# Connector_SFP.net
KiCad netlist of a schematic drawn in Altium Designer
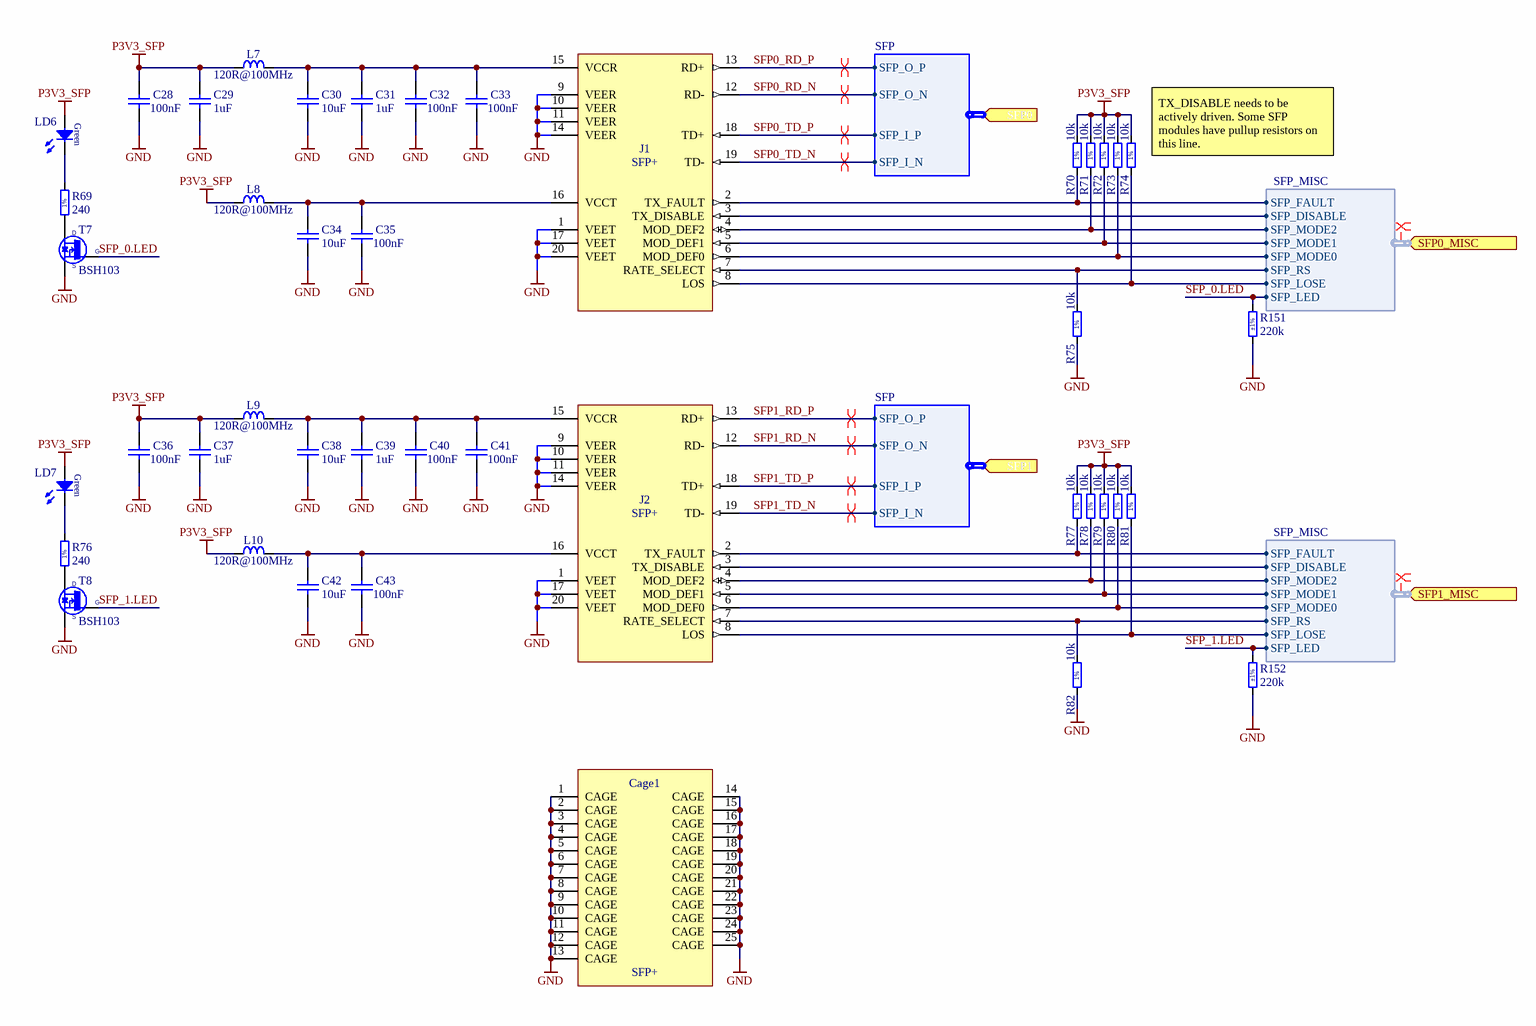
[diagram p0: Connector_SFP.SchDoc]

(export (version "E")
  (design (tool "Eeschema 10.0.6"))
  (components
    (comp (ref "C28")
      (value "100nF")
      (footprint "CAPC1005X55N")
      (description "Non-polarised capacitor")
      (fields
        (field (name "PART NUMBER") "CC0402_100NF_16V_10%_X5R")
        (field (name "VOLTAGE") "16V")
        (field (name "AUTHOR") "CERN DEM JLC")
      )
      (libsource (lib "Capacitors") (part "Capacitor - non polarized"))
    )
    (comp (ref "C29")
      (value "1uF")
      (footprint "CAPC1005X55N")
      (description "Non-polarised capacitor")
      (fields
        (field (name "PART NUMBER") "CC0402_1UF_16V_10%_X5R")
        (field (name "VOLTAGE") "16V")
        (field (name "AUTHOR") "CERN DEM JLC")
      )
      (libsource (lib "Capacitors") (part "Capacitor - non polarized"))
    )
    (comp (ref "C30")
      (value "10uF")
      (footprint "CAPC1608X80N")
      (description "Non-polarised capacitor")
      (fields
        (field (name "PART NUMBER") "CC0603_10UF_16V_20%_X5R")
        (field (name "VOLTAGE") "16V")
        (field (name "AUTHOR") "CERN DEM MR")
      )
      (libsource (lib "Capacitors") (part "Capacitor - non polarized"))
    )
    (comp (ref "C31")
      (value "1uF")
      (footprint "CAPC1005X55N")
      (description "Non-polarised capacitor")
      (fields
        (field (name "PART NUMBER") "CC0402_1UF_16V_10%_X5R")
        (field (name "VOLTAGE") "16V")
        (field (name "AUTHOR") "CERN DEM JLC")
      )
      (libsource (lib "Capacitors") (part "Capacitor - non polarized"))
    )
    (comp (ref "C32")
      (value "100nF")
      (footprint "CAPC1005X55N")
      (description "Non-polarised capacitor")
      (fields
        (field (name "PART NUMBER") "CC0402_100NF_16V_10%_X5R")
        (field (name "VOLTAGE") "16V")
        (field (name "AUTHOR") "CERN DEM JLC")
      )
      (libsource (lib "Capacitors") (part "Capacitor - non polarized"))
    )
    (comp (ref "C33")
      (value "100nF")
      (footprint "CAPC1005X55N")
      (description "Non-polarised capacitor")
      (fields
        (field (name "PART NUMBER") "CC0402_100NF_16V_10%_X5R")
        (field (name "VOLTAGE") "16V")
        (field (name "AUTHOR") "CERN DEM JLC")
      )
      (libsource (lib "Capacitors") (part "Capacitor - non polarized"))
    )
    (comp (ref "C34")
      (value "10uF")
      (footprint "CAPC1608X80N")
      (description "Non-polarised capacitor")
      (fields
        (field (name "PART NUMBER") "CC0603_10UF_16V_20%_X5R")
        (field (name "VOLTAGE") "16V")
        (field (name "AUTHOR") "CERN DEM MR")
      )
      (libsource (lib "Capacitors") (part "Capacitor - non polarized"))
    )
    (comp (ref "C35")
      (value "100nF")
      (footprint "CAPC1005X55N")
      (description "Non-polarised capacitor")
      (fields
        (field (name "PART NUMBER") "CC0402_100NF_16V_10%_X5R")
        (field (name "VOLTAGE") "16V")
        (field (name "AUTHOR") "CERN DEM JLC")
      )
      (libsource (lib "Capacitors") (part "Capacitor - non polarized"))
    )
    (comp (ref "C36")
      (value "100nF")
      (footprint "CAPC1005X55N")
      (description "Non-polarised capacitor")
      (fields
        (field (name "PART NUMBER") "CC0402_100NF_16V_10%_X5R")
        (field (name "VOLTAGE") "16V")
        (field (name "AUTHOR") "CERN DEM JLC")
      )
      (libsource (lib "Capacitors") (part "Capacitor - non polarized"))
    )
    (comp (ref "C37")
      (value "1uF")
      (footprint "CAPC1005X55N")
      (description "Non-polarised capacitor")
      (fields
        (field (name "PART NUMBER") "CC0402_1UF_16V_10%_X5R")
        (field (name "VOLTAGE") "16V")
        (field (name "AUTHOR") "CERN DEM JLC")
      )
      (libsource (lib "Capacitors") (part "Capacitor - non polarized"))
    )
    (comp (ref "C38")
      (value "10uF")
      (footprint "CAPC1608X80N")
      (description "Non-polarised capacitor")
      (fields
        (field (name "PART NUMBER") "CC0603_10UF_16V_20%_X5R")
        (field (name "VOLTAGE") "16V")
        (field (name "AUTHOR") "CERN DEM MR")
      )
      (libsource (lib "Capacitors") (part "Capacitor - non polarized"))
    )
    (comp (ref "C39")
      (value "1uF")
      (footprint "CAPC1005X55N")
      (description "Non-polarised capacitor")
      (fields
        (field (name "PART NUMBER") "CC0402_1UF_16V_10%_X5R")
        (field (name "VOLTAGE") "16V")
        (field (name "AUTHOR") "CERN DEM JLC")
      )
      (libsource (lib "Capacitors") (part "Capacitor - non polarized"))
    )
    (comp (ref "C40")
      (value "100nF")
      (footprint "CAPC1005X55N")
      (description "Non-polarised capacitor")
      (fields
        (field (name "PART NUMBER") "CC0402_100NF_16V_10%_X5R")
        (field (name "VOLTAGE") "16V")
        (field (name "AUTHOR") "CERN DEM JLC")
      )
      (libsource (lib "Capacitors") (part "Capacitor - non polarized"))
    )
    (comp (ref "C41")
      (value "100nF")
      (footprint "CAPC1005X55N")
      (description "Non-polarised capacitor")
      (fields
        (field (name "PART NUMBER") "CC0402_100NF_16V_10%_X5R")
        (field (name "VOLTAGE") "16V")
        (field (name "AUTHOR") "CERN DEM JLC")
      )
      (libsource (lib "Capacitors") (part "Capacitor - non polarized"))
    )
    (comp (ref "C42")
      (value "10uF")
      (footprint "CAPC1608X80N")
      (description "Non-polarised capacitor")
      (fields
        (field (name "PART NUMBER") "CC0603_10UF_16V_20%_X5R")
        (field (name "VOLTAGE") "16V")
        (field (name "AUTHOR") "CERN DEM MR")
      )
      (libsource (lib "Capacitors") (part "Capacitor - non polarized"))
    )
    (comp (ref "C43")
      (value "100nF")
      (footprint "CAPC1005X55N")
      (description "Non-polarised capacitor")
      (fields
        (field (name "PART NUMBER") "CC0402_100NF_16V_10%_X5R")
        (field (name "VOLTAGE") "16V")
        (field (name "AUTHOR") "CERN DEM JLC")
      )
      (libsource (lib "Capacitors") (part "Capacitor - non polarized"))
    )
    (comp (ref "Cage1")
      (value "SFP+")
      (footprint "TYCO_2007263-1")
      (description "SFP 1x2 Cage (25Pins)")
      (fields
        (field (name "PART NUMBER") "TYCO_2007263-1")
        (field (name "MANUFACTURER") "TYCO ELECTRONICS")
        (field (name "AUTHOR") "CERN DEM JLC")
      )
      (libsource (lib "Connectors") (part "SFP 1x2 Cage (25Pins)"))
    )
    (comp (ref "J1")
      (value "SFP+")
      (footprint "MOLEX_74441-0001")
      (description "20 Position SFP  Connector (Small Form-factor Pluggable)")
      (fields
        (field (name "PART NUMBER") "MOLEX_74441-0001")
        (field (name "MANUFACTURER") "MOLEX")
        (field (name "AUTHOR") "CERN DEM MR")
      )
      (libsource (lib "Connectors") (part "SFPx1"))
    )
    (comp (ref "J2")
      (value "SFP+")
      (footprint "MOLEX_74441-0001")
      (description "20 Position SFP  Connector (Small Form-factor Pluggable)")
      (fields
        (field (name "PART NUMBER") "MOLEX_74441-0001")
        (field (name "MANUFACTURER") "MOLEX")
        (field (name "AUTHOR") "CERN DEM MR")
      )
      (libsource (lib "Connectors") (part "SFPx1"))
    )
    (comp (ref "L7")
      (value "120R@100MHz")
      (footprint "INDC1608X65N")
      (description "Inductor")
      (fields
        (field (name "PART NUMBER") "IND0603_MURATA_BLM18SG121TN1D")
        (field (name "POWER") "3A")
        (field (name "AUTHOR") "CERN DEM JLC")
      )
      (libsource (lib "Inductors & Transformers") (part "Inductor"))
    )
    (comp (ref "L8")
      (value "120R@100MHz")
      (footprint "INDC1608X65N")
      (description "Inductor")
      (fields
        (field (name "PART NUMBER") "IND0603_MURATA_BLM18SG121TN1D")
        (field (name "POWER") "3A")
        (field (name "AUTHOR") "CERN DEM JLC")
      )
      (libsource (lib "Inductors & Transformers") (part "Inductor"))
    )
    (comp (ref "L9")
      (value "120R@100MHz")
      (footprint "INDC1608X65N")
      (description "Inductor")
      (fields
        (field (name "PART NUMBER") "IND0603_MURATA_BLM18SG121TN1D")
        (field (name "POWER") "3A")
        (field (name "AUTHOR") "CERN DEM JLC")
      )
      (libsource (lib "Inductors & Transformers") (part "Inductor"))
    )
    (comp (ref "L10")
      (value "120R@100MHz")
      (footprint "INDC1608X65N")
      (description "Inductor")
      (fields
        (field (name "PART NUMBER") "IND0603_MURATA_BLM18SG121TN1D")
        (field (name "POWER") "3A")
        (field (name "AUTHOR") "CERN DEM JLC")
      )
      (libsource (lib "Inductors & Transformers") (part "Inductor"))
    )
    (comp (ref "LD6")
      (value "Green")
      (footprint "LED_AVAGO_HSME-C120")
      (description "LED Green 1C 2A")
      (fields
        (field (name "PART NUMBER") "LED_AVAGO_HSME-C120")
        (field (name "MANUFACTURER") "AVAGO TECHNOLOGIES")
        (field (name "AUTHOR") "CERN DEM JMW")
      )
      (libsource (lib "ICs And Semiconductors") (part "LED Green 1C 2A"))
    )
    (comp (ref "LD7")
      (value "Green")
      (footprint "LED_AVAGO_HSME-C120")
      (description "LED Green 1C 2A")
      (fields
        (field (name "PART NUMBER") "LED_AVAGO_HSME-C120")
        (field (name "MANUFACTURER") "AVAGO TECHNOLOGIES")
        (field (name "AUTHOR") "CERN DEM JMW")
      )
      (libsource (lib "ICs And Semiconductors") (part "LED Green 1C 2A"))
    )
    (comp (ref "R69")
      (value "240")
      (footprint "RESC1005X40N")
      (description "Resistor - 1%")
      (fields
        (field (name "PART NUMBER") "R0402_240R_1%_0.0625W_100PPM")
        (field (name "POWER") "0.0625W")
        (field (name "AUTHOR") "CERN DEM JLC")
      )
      (libsource (lib "Resistors") (part "Resistor - 1%"))
    )
    (comp (ref "R70")
      (value "10k")
      (footprint "RESC1005X40N")
      (description "Resistor - 1%")
      (fields
        (field (name "PART NUMBER") "R0402_10K_1%_0.0625W_100PPM")
        (field (name "POWER") "0.0625W")
        (field (name "AUTHOR") "CERN DEM JLC")
      )
      (libsource (lib "Resistors") (part "Resistor - 1%"))
    )
    (comp (ref "R71")
      (value "10k")
      (footprint "RESC1005X40N")
      (description "Resistor - 1%")
      (fields
        (field (name "PART NUMBER") "R0402_10K_1%_0.0625W_100PPM")
        (field (name "POWER") "0.0625W")
        (field (name "AUTHOR") "CERN DEM JLC")
      )
      (libsource (lib "Resistors") (part "Resistor - 1%"))
    )
    (comp (ref "R72")
      (value "10k")
      (footprint "RESC1005X40N")
      (description "Resistor - 1%")
      (fields
        (field (name "PART NUMBER") "R0402_10K_1%_0.0625W_100PPM")
        (field (name "POWER") "0.0625W")
        (field (name "AUTHOR") "CERN DEM JLC")
      )
      (libsource (lib "Resistors") (part "Resistor - 1%"))
    )
    (comp (ref "R73")
      (value "10k")
      (footprint "RESC1005X40N")
      (description "Resistor - 1%")
      (fields
        (field (name "PART NUMBER") "R0402_10K_1%_0.0625W_100PPM")
        (field (name "POWER") "0.0625W")
        (field (name "AUTHOR") "CERN DEM JLC")
      )
      (libsource (lib "Resistors") (part "Resistor - 1%"))
    )
    (comp (ref "R74")
      (value "10k")
      (footprint "RESC1005X40N")
      (description "Resistor - 1%")
      (fields
        (field (name "PART NUMBER") "R0402_10K_1%_0.0625W_100PPM")
        (field (name "POWER") "0.0625W")
        (field (name "AUTHOR") "CERN DEM JLC")
      )
      (libsource (lib "Resistors") (part "Resistor - 1%"))
    )
    (comp (ref "R75")
      (value "10k")
      (footprint "RESC1005X40N")
      (description "Resistor - 1%")
      (fields
        (field (name "PART NUMBER") "R0402_10K_1%_0.0625W_100PPM")
        (field (name "POWER") "0.0625W")
        (field (name "AUTHOR") "CERN DEM JLC")
      )
      (libsource (lib "Resistors") (part "Resistor - 1%"))
    )
    (comp (ref "R76")
      (value "240")
      (footprint "RESC1005X40N")
      (description "Resistor - 1%")
      (fields
        (field (name "PART NUMBER") "R0402_240R_1%_0.0625W_100PPM")
        (field (name "POWER") "0.0625W")
        (field (name "AUTHOR") "CERN DEM JLC")
      )
      (libsource (lib "Resistors") (part "Resistor - 1%"))
    )
    (comp (ref "R77")
      (value "10k")
      (footprint "RESC1005X40N")
      (description "Resistor - 1%")
      (fields
        (field (name "PART NUMBER") "R0402_10K_1%_0.0625W_100PPM")
        (field (name "POWER") "0.0625W")
        (field (name "AUTHOR") "CERN DEM JLC")
      )
      (libsource (lib "Resistors") (part "Resistor - 1%"))
    )
    (comp (ref "R78")
      (value "10k")
      (footprint "RESC1005X40N")
      (description "Resistor - 1%")
      (fields
        (field (name "PART NUMBER") "R0402_10K_1%_0.0625W_100PPM")
        (field (name "POWER") "0.0625W")
        (field (name "AUTHOR") "CERN DEM JLC")
      )
      (libsource (lib "Resistors") (part "Resistor - 1%"))
    )
    (comp (ref "R79")
      (value "10k")
      (footprint "RESC1005X40N")
      (description "Resistor - 1%")
      (fields
        (field (name "PART NUMBER") "R0402_10K_1%_0.0625W_100PPM")
        (field (name "POWER") "0.0625W")
        (field (name "AUTHOR") "CERN DEM JLC")
      )
      (libsource (lib "Resistors") (part "Resistor - 1%"))
    )
    (comp (ref "R80")
      (value "10k")
      (footprint "RESC1005X40N")
      (description "Resistor - 1%")
      (fields
        (field (name "PART NUMBER") "R0402_10K_1%_0.0625W_100PPM")
        (field (name "POWER") "0.0625W")
        (field (name "AUTHOR") "CERN DEM JLC")
      )
      (libsource (lib "Resistors") (part "Resistor - 1%"))
    )
    (comp (ref "R81")
      (value "10k")
      (footprint "RESC1005X40N")
      (description "Resistor - 1%")
      (fields
        (field (name "PART NUMBER") "R0402_10K_1%_0.0625W_100PPM")
        (field (name "POWER") "0.0625W")
        (field (name "AUTHOR") "CERN DEM JLC")
      )
      (libsource (lib "Resistors") (part "Resistor - 1%"))
    )
    (comp (ref "R82")
      (value "10k")
      (footprint "RESC1005X40N")
      (description "Resistor - 1%")
      (fields
        (field (name "PART NUMBER") "R0402_10K_1%_0.0625W_100PPM")
        (field (name "POWER") "0.0625W")
        (field (name "AUTHOR") "CERN DEM JLC")
      )
      (libsource (lib "Resistors") (part "Resistor - 1%"))
    )
    (comp (ref "R151")
      (value "220k")
      (footprint "RESC1005X40N")
      (description "Resistor - 1%")
      (fields
        (field (name "TOLERANCE") "±1%")
        (field (name "PART NUMBER") "R0402_220K_1%_0.0625W_100PPM")
        (field (name "POWER") "0.0625W")
        (field (name "AUTHOR") "CERN DEM JLC")
      )
      (libsource (lib "Resistors") (part "Resistor - 1%"))
    )
    (comp (ref "R152")
      (value "220k")
      (footprint "RESC1005X40N")
      (description "Resistor - 1%")
      (fields
        (field (name "TOLERANCE") "±1%")
        (field (name "PART NUMBER") "R0402_220K_1%_0.0625W_100PPM")
        (field (name "POWER") "0.0625W")
        (field (name "AUTHOR") "CERN DEM JLC")
      )
      (libsource (lib "Resistors") (part "Resistor - 1%"))
    )
    (comp (ref "T7")
      (value "BSH103")
      (footprint "SOT95P230X110-3N")
      (description "N-CHANNEL MOSFET WITH DIODE")
      (fields (field (name "MANUFACTURER") "NEXPERIA") (field (name "AUTHOR") "CERN DEM JLC"))
      (libsource (lib "ICs And Semiconductors") (part "N-MOSFET-D 1G 2S 3D"))
    )
    (comp (ref "T8")
      (value "BSH103")
      (footprint "SOT95P230X110-3N")
      (description "N-CHANNEL MOSFET WITH DIODE")
      (fields (field (name "MANUFACTURER") "NEXPERIA") (field (name "AUTHOR") "CERN DEM JLC"))
      (libsource (lib "ICs And Semiconductors") (part "N-MOSFET-D 1G 2S 3D"))
    )
  )
  (nets
    (net (code "3") (name "/SFP0_RD_N") (class "Default")
      (node (ref "J1") (pin "12") (pinfunction "RD-_12") (pintype "output"))
    )
    (net (code "4") (name "/SFP0_RD_P") (class "Default")
      (node (ref "J1") (pin "13") (pinfunction "RD+_13") (pintype "output"))
    )
    (net (code "5") (name "/SFP0_TD_N") (class "Default")
      (node (ref "J1") (pin "19") (pinfunction "TD-_19") (pintype "input"))
    )
    (net (code "6") (name "/SFP0_TD_P") (class "Default")
      (node (ref "J1") (pin "18") (pinfunction "TD+_18") (pintype "input"))
    )
    (net (code "7") (name "/SFP1_RD_N") (class "Default")
      (node (ref "J2") (pin "12") (pinfunction "RD-_12") (pintype "output"))
    )
    (net (code "8") (name "/SFP1_RD_P") (class "Default")
      (node (ref "J2") (pin "13") (pinfunction "RD+_13") (pintype "output"))
    )
    (net (code "9") (name "/SFP1_TD_N") (class "Default")
      (node (ref "J2") (pin "19") (pinfunction "TD-_19") (pintype "input"))
    )
    (net (code "10") (name "/SFP1_TD_P") (class "Default")
      (node (ref "J2") (pin "18") (pinfunction "TD+_18") (pintype "input"))
    )
    (net (code "11") (name "/SFP_0.LED") (class "Default")
      (node (ref "R151") (pin "2") (pinfunction "2_2") (pintype "passive"))
      (node (ref "T7") (pin "1") (pinfunction "G_1") (pintype "passive"))
    )
    (net (code "12") (name "/SFP_1.LED") (class "Default")
      (node (ref "R152") (pin "2") (pinfunction "2_2") (pintype "passive"))
      (node (ref "T8") (pin "1") (pinfunction "G_1") (pintype "passive"))
    )
    (net (code "15") (name "GND") (class "Default")
      (node (ref "C28") (pin "1") (pinfunction "1_1") (pintype "passive"))
      (node (ref "C29") (pin "1") (pinfunction "1_1") (pintype "passive"))
      (node (ref "C30") (pin "1") (pinfunction "1_1") (pintype "passive"))
      (node (ref "C31") (pin "1") (pinfunction "1_1") (pintype "passive"))
      (node (ref "C32") (pin "1") (pinfunction "1_1") (pintype "passive"))
      (node (ref "C33") (pin "1") (pinfunction "1_1") (pintype "passive"))
      (node (ref "C34") (pin "1") (pinfunction "1_1") (pintype "passive"))
      (node (ref "C35") (pin "1") (pinfunction "1_1") (pintype "passive"))
      (node (ref "C36") (pin "1") (pinfunction "1_1") (pintype "passive"))
      (node (ref "C37") (pin "1") (pinfunction "1_1") (pintype "passive"))
      (node (ref "C38") (pin "1") (pinfunction "1_1") (pintype "passive"))
      (node (ref "C39") (pin "1") (pinfunction "1_1") (pintype "passive"))
      (node (ref "C40") (pin "1") (pinfunction "1_1") (pintype "passive"))
      (node (ref "C41") (pin "1") (pinfunction "1_1") (pintype "passive"))
      (node (ref "C42") (pin "1") (pinfunction "1_1") (pintype "passive"))
      (node (ref "C43") (pin "1") (pinfunction "1_1") (pintype "passive"))
      (node (ref "Cage1") (pin "1") (pinfunction "CAGE_1") (pintype "power_in"))
      (node (ref "Cage1") (pin "10") (pinfunction "CAGE_10") (pintype "power_in"))
      (node (ref "Cage1") (pin "11") (pinfunction "CAGE_11") (pintype "power_in"))
      (node (ref "Cage1") (pin "12") (pinfunction "CAGE_12") (pintype "power_in"))
      (node (ref "Cage1") (pin "13") (pinfunction "CAGE_13") (pintype "power_in"))
      (node (ref "Cage1") (pin "14") (pinfunction "CAGE_14") (pintype "power_in"))
      (node (ref "Cage1") (pin "15") (pinfunction "CAGE_15") (pintype "power_in"))
      (node (ref "Cage1") (pin "16") (pinfunction "CAGE_16") (pintype "power_in"))
      (node (ref "Cage1") (pin "17") (pinfunction "CAGE_17") (pintype "power_in"))
      (node (ref "Cage1") (pin "18") (pinfunction "CAGE_18") (pintype "power_in"))
      (node (ref "Cage1") (pin "19") (pinfunction "CAGE_19") (pintype "power_in"))
      (node (ref "Cage1") (pin "2") (pinfunction "CAGE_2") (pintype "power_in"))
      (node (ref "Cage1") (pin "20") (pinfunction "CAGE_20") (pintype "power_in"))
      (node (ref "Cage1") (pin "21") (pinfunction "CAGE_21") (pintype "power_in"))
      (node (ref "Cage1") (pin "22") (pinfunction "CAGE_22") (pintype "power_in"))
      (node (ref "Cage1") (pin "23") (pinfunction "CAGE_23") (pintype "power_in"))
      (node (ref "Cage1") (pin "24") (pinfunction "CAGE_24") (pintype "power_in"))
      (node (ref "Cage1") (pin "25") (pinfunction "CAGE_25") (pintype "power_in"))
      (node (ref "Cage1") (pin "3") (pinfunction "CAGE_3") (pintype "power_in"))
      (node (ref "Cage1") (pin "4") (pinfunction "CAGE_4") (pintype "power_in"))
      (node (ref "Cage1") (pin "5") (pinfunction "CAGE_5") (pintype "power_in"))
      (node (ref "Cage1") (pin "6") (pinfunction "CAGE_6") (pintype "power_in"))
      (node (ref "Cage1") (pin "7") (pinfunction "CAGE_7") (pintype "power_in"))
      (node (ref "Cage1") (pin "8") (pinfunction "CAGE_8") (pintype "power_in"))
      (node (ref "Cage1") (pin "9") (pinfunction "CAGE_9") (pintype "power_in"))
      (node (ref "J1") (pin "1") (pinfunction "VEET_1") (pintype "power_in"))
      (node (ref "J1") (pin "10") (pinfunction "VEER_10") (pintype "power_in"))
      (node (ref "J1") (pin "11") (pinfunction "VEER_11") (pintype "power_in"))
      (node (ref "J1") (pin "14") (pinfunction "VEER_14") (pintype "power_in"))
      (node (ref "J1") (pin "17") (pinfunction "VEET_17") (pintype "power_in"))
      (node (ref "J1") (pin "20") (pinfunction "VEET_20") (pintype "power_in"))
      (node (ref "J1") (pin "9") (pinfunction "VEER_9") (pintype "power_in"))
      (node (ref "J2") (pin "1") (pinfunction "VEET_1") (pintype "power_in"))
      (node (ref "J2") (pin "10") (pinfunction "VEER_10") (pintype "power_in"))
      (node (ref "J2") (pin "11") (pinfunction "VEER_11") (pintype "power_in"))
      (node (ref "J2") (pin "14") (pinfunction "VEER_14") (pintype "power_in"))
      (node (ref "J2") (pin "17") (pinfunction "VEET_17") (pintype "power_in"))
      (node (ref "J2") (pin "20") (pinfunction "VEET_20") (pintype "power_in"))
      (node (ref "J2") (pin "9") (pinfunction "VEER_9") (pintype "power_in"))
      (node (ref "R151") (pin "1") (pinfunction "1_1") (pintype "passive"))
      (node (ref "R152") (pin "1") (pinfunction "1_1") (pintype "passive"))
      (node (ref "R75") (pin "1") (pinfunction "1_1") (pintype "passive"))
      (node (ref "R82") (pin "1") (pinfunction "1_1") (pintype "passive"))
      (node (ref "T7") (pin "2") (pinfunction "S_2") (pintype "passive"))
      (node (ref "T8") (pin "2") (pinfunction "S_2") (pintype "passive"))
    )
    (net (code "16") (name "Net-(J1-LOS)") (class "Default")
      (node (ref "J1") (pin "8") (pinfunction "LOS_8") (pintype "output"))
      (node (ref "R74") (pin "1") (pinfunction "1_1") (pintype "passive"))
    )
    (net (code "17") (name "Net-(J1-MOD_DEF0)") (class "Default")
      (node (ref "J1") (pin "6") (pinfunction "MOD_DEF0_6") (pintype "output"))
      (node (ref "R73") (pin "1") (pinfunction "1_1") (pintype "passive"))
    )
    (net (code "18") (name "Net-(J1-MOD_DEF1)") (class "Default")
      (node (ref "J1") (pin "5") (pinfunction "MOD_DEF1_5") (pintype "input"))
      (node (ref "R72") (pin "1") (pinfunction "1_1") (pintype "passive"))
    )
    (net (code "19") (name "Net-(J1-MOD_DEF2)") (class "Default")
      (node (ref "J1") (pin "4") (pinfunction "MOD_DEF2_4") (pintype "bidirectional"))
      (node (ref "R71") (pin "1") (pinfunction "1_1") (pintype "passive"))
    )
    (net (code "20") (name "Net-(J1-RATE_SELECT)") (class "Default")
      (node (ref "J1") (pin "7") (pinfunction "RATE_SELECT_7") (pintype "input"))
      (node (ref "R75") (pin "2") (pinfunction "2_2") (pintype "passive"))
    )
    (net (code "21") (name "Net-(J1-TX_FAULT)") (class "Default")
      (node (ref "J1") (pin "2") (pinfunction "TX_FAULT_2") (pintype "output"))
      (node (ref "R70") (pin "1") (pinfunction "1_1") (pintype "passive"))
    )
    (net (code "22") (name "Net-(J1-VCCR)") (class "Default")
      (node (ref "C30") (pin "2") (pinfunction "2_2") (pintype "passive"))
      (node (ref "C31") (pin "2") (pinfunction "2_2") (pintype "passive"))
      (node (ref "C32") (pin "2") (pinfunction "2_2") (pintype "passive"))
      (node (ref "C33") (pin "2") (pinfunction "2_2") (pintype "passive"))
      (node (ref "J1") (pin "15") (pinfunction "VCCR_15") (pintype "power_in"))
      (node (ref "L7") (pin "2") (pinfunction "2_2") (pintype "passive"))
    )
    (net (code "23") (name "Net-(J1-VCCT)") (class "Default")
      (node (ref "C34") (pin "2") (pinfunction "2_2") (pintype "passive"))
      (node (ref "C35") (pin "2") (pinfunction "2_2") (pintype "passive"))
      (node (ref "J1") (pin "16") (pinfunction "VCCT_16") (pintype "power_in"))
      (node (ref "L8") (pin "2") (pinfunction "2_2") (pintype "passive"))
    )
    (net (code "24") (name "Net-(J2-LOS)") (class "Default")
      (node (ref "J2") (pin "8") (pinfunction "LOS_8") (pintype "output"))
      (node (ref "R81") (pin "1") (pinfunction "1_1") (pintype "passive"))
    )
    (net (code "25") (name "Net-(J2-MOD_DEF0)") (class "Default")
      (node (ref "J2") (pin "6") (pinfunction "MOD_DEF0_6") (pintype "output"))
      (node (ref "R80") (pin "1") (pinfunction "1_1") (pintype "passive"))
    )
    (net (code "26") (name "Net-(J2-MOD_DEF1)") (class "Default")
      (node (ref "J2") (pin "5") (pinfunction "MOD_DEF1_5") (pintype "input"))
      (node (ref "R79") (pin "1") (pinfunction "1_1") (pintype "passive"))
    )
    (net (code "27") (name "Net-(J2-MOD_DEF2)") (class "Default")
      (node (ref "J2") (pin "4") (pinfunction "MOD_DEF2_4") (pintype "bidirectional"))
      (node (ref "R78") (pin "1") (pinfunction "1_1") (pintype "passive"))
    )
    (net (code "28") (name "Net-(J2-RATE_SELECT)") (class "Default")
      (node (ref "J2") (pin "7") (pinfunction "RATE_SELECT_7") (pintype "input"))
      (node (ref "R82") (pin "2") (pinfunction "2_2") (pintype "passive"))
    )
    (net (code "29") (name "Net-(J2-TX_FAULT)") (class "Default")
      (node (ref "J2") (pin "2") (pinfunction "TX_FAULT_2") (pintype "output"))
      (node (ref "R77") (pin "1") (pinfunction "1_1") (pintype "passive"))
    )
    (net (code "30") (name "Net-(J2-VCCR)") (class "Default")
      (node (ref "C38") (pin "2") (pinfunction "2_2") (pintype "passive"))
      (node (ref "C39") (pin "2") (pinfunction "2_2") (pintype "passive"))
      (node (ref "C40") (pin "2") (pinfunction "2_2") (pintype "passive"))
      (node (ref "C41") (pin "2") (pinfunction "2_2") (pintype "passive"))
      (node (ref "J2") (pin "15") (pinfunction "VCCR_15") (pintype "power_in"))
      (node (ref "L9") (pin "2") (pinfunction "2_2") (pintype "passive"))
    )
    (net (code "31") (name "Net-(J2-VCCT)") (class "Default")
      (node (ref "C42") (pin "2") (pinfunction "2_2") (pintype "passive"))
      (node (ref "C43") (pin "2") (pinfunction "2_2") (pintype "passive"))
      (node (ref "J2") (pin "16") (pinfunction "VCCT_16") (pintype "power_in"))
      (node (ref "L10") (pin "2") (pinfunction "2_2") (pintype "passive"))
    )
    (net (code "32") (name "Net-(LD6-C)") (class "Default")
      (node (ref "LD6") (pin "1") (pinfunction "C_1") (pintype "passive"))
      (node (ref "R69") (pin "2") (pinfunction "2_2") (pintype "passive"))
    )
    (net (code "33") (name "Net-(LD7-C)") (class "Default")
      (node (ref "LD7") (pin "1") (pinfunction "C_1") (pintype "passive"))
      (node (ref "R76") (pin "2") (pinfunction "2_2") (pintype "passive"))
    )
    (net (code "34") (name "Net-(T7-D)") (class "Default")
      (node (ref "R69") (pin "1") (pinfunction "1_1") (pintype "passive"))
      (node (ref "T7") (pin "3") (pinfunction "D_3") (pintype "passive"))
    )
    (net (code "35") (name "Net-(T8-D)") (class "Default")
      (node (ref "R76") (pin "1") (pinfunction "1_1") (pintype "passive"))
      (node (ref "T8") (pin "3") (pinfunction "D_3") (pintype "passive"))
    )
    (net (code "36") (name "P3V3_SFP") (class "Default")
      (node (ref "C28") (pin "2") (pinfunction "2_2") (pintype "passive"))
      (node (ref "C29") (pin "2") (pinfunction "2_2") (pintype "passive"))
      (node (ref "C36") (pin "2") (pinfunction "2_2") (pintype "passive"))
      (node (ref "C37") (pin "2") (pinfunction "2_2") (pintype "passive"))
      (node (ref "L10") (pin "1") (pinfunction "1_1") (pintype "passive"))
      (node (ref "L7") (pin "1") (pinfunction "1_1") (pintype "passive"))
      (node (ref "L8") (pin "1") (pinfunction "1_1") (pintype "passive"))
      (node (ref "L9") (pin "1") (pinfunction "1_1") (pintype "passive"))
      (node (ref "LD6") (pin "2") (pinfunction "A_2") (pintype "passive"))
      (node (ref "LD7") (pin "2") (pinfunction "A_2") (pintype "passive"))
      (node (ref "R70") (pin "2") (pinfunction "2_2") (pintype "passive"))
      (node (ref "R71") (pin "2") (pinfunction "2_2") (pintype "passive"))
      (node (ref "R72") (pin "2") (pinfunction "2_2") (pintype "passive"))
      (node (ref "R73") (pin "2") (pinfunction "2_2") (pintype "passive"))
      (node (ref "R74") (pin "2") (pinfunction "2_2") (pintype "passive"))
      (node (ref "R77") (pin "2") (pinfunction "2_2") (pintype "passive"))
      (node (ref "R78") (pin "2") (pinfunction "2_2") (pintype "passive"))
      (node (ref "R79") (pin "2") (pinfunction "2_2") (pintype "passive"))
      (node (ref "R80") (pin "2") (pinfunction "2_2") (pintype "passive"))
      (node (ref "R81") (pin "2") (pinfunction "2_2") (pintype "passive"))
    )
    (net (code "37") (name "unconnected-(J1-TX_DISABLE-Pad3)") (class "Default")
      (node (ref "J1") (pin "3") (pinfunction "TX_DISABLE_3") (pintype "input"))
    )
    (net (code "38") (name "unconnected-(J2-TX_DISABLE-Pad3)") (class "Default")
      (node (ref "J2") (pin "3") (pinfunction "TX_DISABLE_3") (pintype "input"))
    )
  )
)
